# PowerSupply.net
KiCad netlist of a schematic drawn in Altium Designer
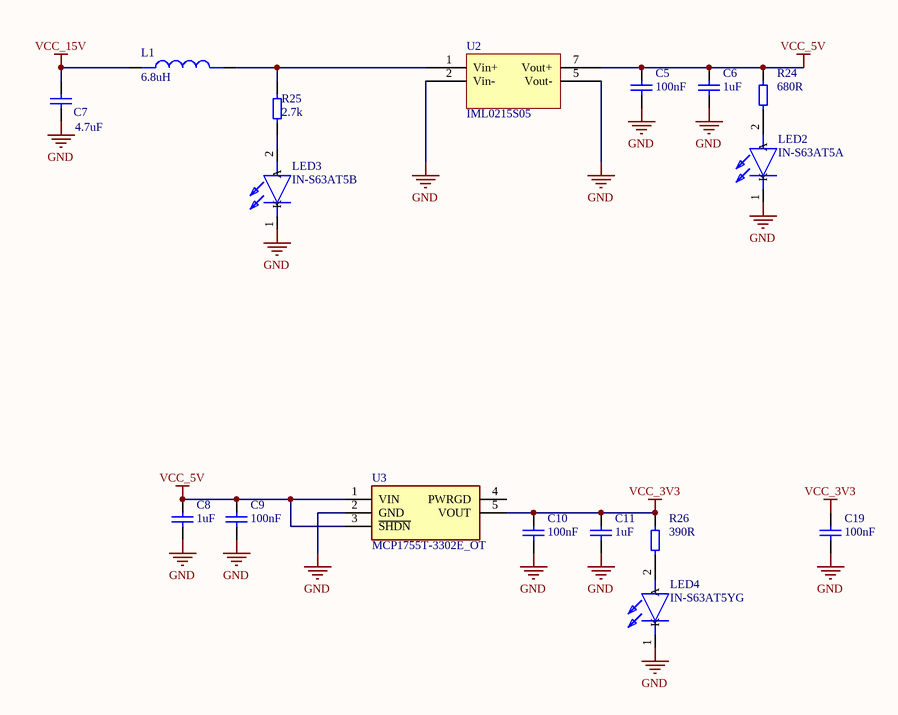
[diagram p0: PowerSupply.SchDoc]

(export (version "E")
  (design (tool "Eeschema 10.0.6"))
  (components
    (comp (ref "C5")
      (value "100nF")
      (footprint "0603-Capacitor")
      (description "Capacitor")
      (fields (field (name "PART NUMBER") "C0603"))
      (libsource (lib "ZUIAM_LIB") (part "Capacitor"))
    )
    (comp (ref "C6")
      (value "1uF")
      (footprint "0603-Capacitor")
      (description "Capacitor")
      (fields (field (name "PART NUMBER") "C0603"))
      (libsource (lib "ZUIAM_LIB") (part "Capacitor"))
    )
    (comp (ref "C7")
      (value "4.7uF")
      (footprint "1206-Capacitor")
      (description "Capacitor")
      (fields (field (name "PART NUMBER") "C1206"))
      (libsource (lib "ZUIAM_LIB") (part "Capacitor"))
    )
    (comp (ref "C8")
      (value "1uF")
      (footprint "0603-Capacitor")
      (description "Capacitor")
      (fields (field (name "PART NUMBER") "C0603"))
      (libsource (lib "ZUIAM_LIB") (part "Capacitor"))
    )
    (comp (ref "C9")
      (value "100nF")
      (footprint "0603-Capacitor")
      (description "Capacitor")
      (fields (field (name "PART NUMBER") "C0603"))
      (libsource (lib "ZUIAM_LIB") (part "Capacitor"))
    )
    (comp (ref "C10")
      (value "100nF")
      (footprint "0603-Capacitor")
      (description "Capacitor")
      (fields (field (name "PART NUMBER") "C0603"))
      (libsource (lib "ZUIAM_LIB") (part "Capacitor"))
    )
    (comp (ref "C11")
      (value "1uF")
      (footprint "0603-Capacitor")
      (description "Capacitor")
      (fields (field (name "PART NUMBER") "C0603"))
      (libsource (lib "ZUIAM_LIB") (part "Capacitor"))
    )
    (comp (ref "C19")
      (value "100nF")
      (footprint "0603-Capacitor")
      (description "Capacitor")
      (fields (field (name "PART NUMBER") "C0603"))
      (libsource (lib "ZUIAM_LIB") (part "Capacitor"))
    )
    (comp (ref "L1")
      (value "6.8uH")
      (footprint "NRH2410T6R8MN")
      (description "Chip Inductor")
      (fields (field (name "PART NUMBER") "NRH2410T6R8MN") (field (name "MANUFACTURER") "Taiyo Yuden"))
      (libsource (lib "ZUIAM_LIB") (part "Inductor"))
    )
    (comp (ref "LED2")
      (value "IN-S63AT5A")
      (footprint "LEDM168X39N")
      (description "LED")
      (fields (field (name "MOUSER PART NUMBER") "743-IN-S63AT5G"))
      (libsource (lib "mouser") (part "IN-S63AT5G"))
    )
    (comp (ref "LED3")
      (value "IN-S63AT5B")
      (footprint "LEDM168X39N")
      (description "LED")
      (fields (field (name "MOUSER PART NUMBER") "743-IN-S63AT5G"))
      (libsource (lib "mouser") (part "IN-S63AT5G"))
    )
    (comp (ref "LED4")
      (value "IN-S63AT5YG")
      (footprint "LEDM168X39N")
      (description "LED")
      (fields (field (name "MOUSER PART NUMBER") "743-IN-S63AT5G"))
      (libsource (lib "mouser") (part "IN-S63AT5G"))
    )
    (comp (ref "R24")
      (value "680R")
      (footprint "0603-Resistor")
      (description "Resistor")
      (fields (field (name "PART NUMBER") "R0603"))
      (libsource (lib "ZUIAM_LIB") (part "Resistor"))
    )
    (comp (ref "R25")
      (value "2.7k")
      (footprint "0805-Resistor")
      (description "Resistor")
      (fields (field (name "PART NUMBER") "R0805"))
      (libsource (lib "ZUIAM_LIB") (part "Resistor"))
    )
    (comp (ref "R26")
      (value "390R")
      (footprint "0603-Resistor")
      (description "Resistor")
      (fields (field (name "PART NUMBER") "R0603"))
      (libsource (lib "ZUIAM_LIB") (part "Resistor"))
    )
    (comp (ref "U2")
      (value "IML0215S05")
      (footprint "IML02S")
      (description "XP power converter 15V->5V, 400mA")
      (fields (field (name "MANUFACTURER") "XP Power"))
      (libsource (lib "externalModules") (part "IML0215S05"))
    )
    (comp (ref "U3")
      (value "MCP1755T-3302E_OT")
      (footprint "SOT95P270X145-5N")
      (description "Undefined or Miscellaneous")
      (fields (field (name "MANUFACTURER_PART_NUMBER") "MCP1755T-3302E/OT"))
      (libsource (lib "mouser") (part "MCP1755T-3302E_OT"))
    )
  )
  (nets
    (net (code "1") (name "GND") (class "Default")
      (node (ref "C10") (pin "2") (pinfunction "2_2") (pintype "passive"))
      (node (ref "C11") (pin "2") (pinfunction "2_2") (pintype "passive"))
      (node (ref "C19") (pin "2") (pinfunction "2_2") (pintype "passive"))
      (node (ref "C5") (pin "2") (pinfunction "2_2") (pintype "passive"))
      (node (ref "C6") (pin "2") (pinfunction "2_2") (pintype "passive"))
      (node (ref "C7") (pin "2") (pinfunction "2_2") (pintype "passive"))
      (node (ref "C8") (pin "2") (pinfunction "2_2") (pintype "passive"))
      (node (ref "C9") (pin "2") (pinfunction "2_2") (pintype "passive"))
      (node (ref "LED2") (pin "1") (pinfunction "K_1") (pintype "passive"))
      (node (ref "LED3") (pin "1") (pinfunction "K_1") (pintype "passive"))
      (node (ref "LED4") (pin "1") (pinfunction "K_1") (pintype "passive"))
      (node (ref "U2") (pin "2") (pinfunction "Vin-_2") (pintype "passive"))
      (node (ref "U2") (pin "5") (pinfunction "Vout-_5") (pintype "passive"))
      (node (ref "U3") (pin "2") (pinfunction "GND_2") (pintype "passive"))
    )
    (net (code "2") (name "Net-(L1-RF-OUT)") (class "Default")
      (node (ref "L1") (pin "2") (pinfunction "RF-OUT_2") (pintype "passive"))
      (node (ref "R25") (pin "2") (pinfunction "2_2") (pintype "passive"))
      (node (ref "U2") (pin "1") (pinfunction "Vin+_1") (pintype "passive"))
    )
    (net (code "3") (name "Net-(LED2-A)") (class "Default")
      (node (ref "LED2") (pin "2") (pinfunction "A_2") (pintype "passive"))
      (node (ref "R24") (pin "1") (pinfunction "1_1") (pintype "passive"))
    )
    (net (code "4") (name "Net-(LED3-A)") (class "Default")
      (node (ref "LED3") (pin "2") (pinfunction "A_2") (pintype "passive"))
      (node (ref "R25") (pin "1") (pinfunction "1_1") (pintype "passive"))
    )
    (net (code "5") (name "Net-(LED4-A)") (class "Default")
      (node (ref "LED4") (pin "2") (pinfunction "A_2") (pintype "passive"))
      (node (ref "R26") (pin "1") (pinfunction "1_1") (pintype "passive"))
    )
    (net (code "6") (name "VCC_3V3") (class "Default")
      (node (ref "C10") (pin "1") (pinfunction "1_1") (pintype "passive"))
      (node (ref "C11") (pin "1") (pinfunction "1_1") (pintype "passive"))
      (node (ref "C19") (pin "1") (pinfunction "1_1") (pintype "passive"))
      (node (ref "R26") (pin "2") (pinfunction "2_2") (pintype "passive"))
      (node (ref "U3") (pin "5") (pinfunction "VOUT_5") (pintype "passive"))
    )
    (net (code "7") (name "VCC_5V") (class "Default")
      (node (ref "C5") (pin "1") (pinfunction "1_1") (pintype "passive"))
      (node (ref "C6") (pin "1") (pinfunction "1_1") (pintype "passive"))
      (node (ref "C8") (pin "1") (pinfunction "1_1") (pintype "passive"))
      (node (ref "C9") (pin "1") (pinfunction "1_1") (pintype "passive"))
      (node (ref "R24") (pin "2") (pinfunction "2_2") (pintype "passive"))
      (node (ref "U2") (pin "7") (pinfunction "Vout+_7") (pintype "passive"))
      (node (ref "U3") (pin "1") (pinfunction "VIN_1") (pintype "passive"))
      (node (ref "U3") (pin "3") (pinfunction "~{SHDN}_3") (pintype "passive"))
    )
    (net (code "8") (name "VCC_15V") (class "Default")
      (node (ref "C7") (pin "1") (pinfunction "1_1") (pintype "passive"))
      (node (ref "L1") (pin "1") (pinfunction "RF-IN_1") (pintype "passive"))
    )
    (net (code "9") (name "unconnected-(U3-PWRGD-Pad4)") (class "Default")
      (node (ref "U3") (pin "4") (pinfunction "PWRGD_4") (pintype "passive"))
    )
  )
)
